# Driver_Channel_DRV8825.net
KiCad netlist of a schematic drawn in Altium Designer
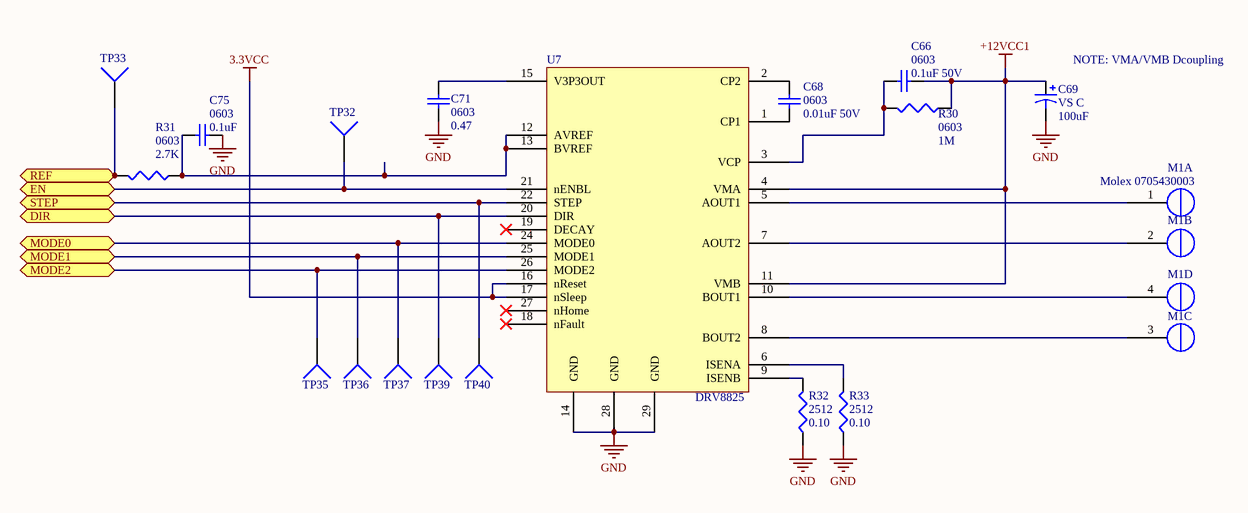
[diagram p0: Driver Channel DRV8825.SchDoc]

(export (version "E")
  (design (tool "Eeschema 10.0.6"))
  (components
    (comp (ref "C66")
      (value "0603")
      (footprint "1608[0603]")
      (description "Capacitor (Semiconductor SIM Model)")
      (fields (field (name "ALTIUM_VALUE") "0.1uF 50V") (field (name "PUBLISHER") "Altium Limited"))
      (libsource (lib "Miscellaneous Devices") (part "Cap Semi"))
    )
    (comp (ref "C68")
      (value "0603")
      (footprint "1608[0603]")
      (description "Capacitor (Semiconductor SIM Model)")
      (fields (field (name "ALTIUM_VALUE") "0.01uF 50V") (field (name "PUBLISHER") "Altium Limited"))
      (libsource (lib "Miscellaneous Devices") (part "Cap Semi"))
    )
    (comp (ref "C69")
      (value "VS C")
      (footprint "Panasonic VS C")
      (description "Polarized Capacitor (Radial)")
      (fields (field (name "ALTIUM_VALUE") "100uF") (field (name "PUBLISHER") "Altium Limited"))
      (libsource (lib "Miscellaneous Devices") (part "Cap Pol1"))
    )
    (comp (ref "C71")
      (value "0603")
      (footprint "1608[0603]")
      (description "Capacitor (Semiconductor SIM Model)")
      (fields (field (name "ALTIUM_VALUE") "0.47") (field (name "PUBLISHER") "Altium Limited"))
      (libsource (lib "Miscellaneous Devices") (part "Cap Semi"))
    )
    (comp (ref "C75")
      (value "0603")
      (footprint "1608[0603]")
      (description "Capacitor (Semiconductor SIM Model)")
      (fields (field (name "ALTIUM_VALUE") "0.1uF") (field (name "PUBLISHER") "Altium Limited"))
      (libsource (lib "Miscellaneous Devices") (part "Cap Semi"))
    )
    (comp (ref "M1")
      (value "Molex 0705430003")
      (footprint "4POL254")
      (description "Molex 4 Pin Clip Connector")
      (libsource (lib "ZMBo Schematic Library") (part "Molex 0705430003 Alt"))
    )
    (comp (ref "R30")
      (value "0603")
      (footprint "J1-0603")
      (description "Resistor")
      (fields (field (name "ALTIUM_VALUE") "1M") (field (name "PUBLISHER") "Altium Limited"))
      (libsource (lib "Miscellaneous Devices") (part "Res3"))
    )
    (comp (ref "R31")
      (value "0603")
      (footprint "J1-0603")
      (description "Resistor")
      (fields (field (name "ALTIUM_VALUE") "2.7K") (field (name "PUBLISHER") "Altium Limited"))
      (libsource (lib "Miscellaneous Devices") (part "Res3"))
    )
    (comp (ref "R32")
      (value "2512")
      (footprint "Resistor2512")
      (description "Resistor")
      (fields (field (name "ALTIUM_VALUE") "0.10") (field (name "PUBLISHER") "Altium Limited"))
      (libsource (lib "Miscellaneous Devices") (part "Res3"))
    )
    (comp (ref "R33")
      (value "2512")
      (footprint "Resistor2512")
      (description "Resistor")
      (fields (field (name "ALTIUM_VALUE") "0.10") (field (name "PUBLISHER") "Altium Limited"))
      (libsource (lib "Miscellaneous Devices") (part "Res3"))
    )
    (comp (ref "TP32")
      (value "TP4")
      (footprint "TP-2")
      (description "Socket")
      (fields (field (name "PUBLISHER") "Altium Limited"))
      (libsource (lib "ZMBo Schematic Library") (part "Socket"))
    )
    (comp (ref "TP33")
      (value "TP4")
      (footprint "TP-2")
      (description "Socket")
      (fields (field (name "PUBLISHER") "Altium Limited"))
      (libsource (lib "ZMBo Schematic Library") (part "Socket"))
    )
    (comp (ref "TP35")
      (value "TP4")
      (footprint "TP-2")
      (description "Socket")
      (fields (field (name "PUBLISHER") "Altium Limited"))
      (libsource (lib "ZMBo Schematic Library") (part "Socket"))
    )
    (comp (ref "TP36")
      (value "TP4")
      (footprint "TP-2")
      (description "Socket")
      (fields (field (name "PUBLISHER") "Altium Limited"))
      (libsource (lib "ZMBo Schematic Library") (part "Socket"))
    )
    (comp (ref "TP37")
      (value "TP4")
      (footprint "TP-2")
      (description "Socket")
      (fields (field (name "PUBLISHER") "Altium Limited"))
      (libsource (lib "ZMBo Schematic Library") (part "Socket"))
    )
    (comp (ref "TP39")
      (value "TP4")
      (footprint "TP-2")
      (description "Socket")
      (fields (field (name "PUBLISHER") "Altium Limited"))
      (libsource (lib "ZMBo Schematic Library") (part "Socket"))
    )
    (comp (ref "TP40")
      (value "TP4")
      (footprint "TP-2")
      (description "Socket")
      (fields (field (name "PUBLISHER") "Altium Limited"))
      (libsource (lib "ZMBo Schematic Library") (part "Socket"))
    )
    (comp (ref "U7")
      (value "DRV8825")
      (footprint "DRV8825")
      (description "DRV8825 Ti Stepper Driver")
      (libsource (lib "ZMBo Schematic Library") (part "DRV8825"))
    )
  )
  (nets
    (net (code "1") (name "+12VCC1") (class "Default")
      (node (ref "C66") (pin "1") (pinfunction "1_1") (pintype "passive"))
      (node (ref "C69") (pin "1") (pinfunction "1_1") (pintype "passive"))
      (node (ref "R30") (pin "1") (pinfunction "1_1") (pintype "passive"))
      (node (ref "U7") (pin "11") (pinfunction "VMB_11") (pintype "passive"))
      (node (ref "U7") (pin "4") (pinfunction "VMA_4") (pintype "passive"))
    )
    (net (code "2") (name "/DIR") (class "Default")
      (node (ref "TP39") (pin "1") (pinfunction "1_1") (pintype "passive"))
      (node (ref "U7") (pin "20") (pinfunction "DIR_20") (pintype "passive"))
    )
    (net (code "3") (name "/EN") (class "Default")
      (node (ref "TP32") (pin "1") (pinfunction "1_1") (pintype "passive"))
      (node (ref "U7") (pin "21") (pinfunction "nENBL_21") (pintype "passive"))
    )
    (net (code "4") (name "/MODE0") (class "Default")
      (node (ref "TP37") (pin "1") (pinfunction "1_1") (pintype "passive"))
      (node (ref "U7") (pin "24") (pinfunction "MODE0_24") (pintype "passive"))
    )
    (net (code "5") (name "/MODE1") (class "Default")
      (node (ref "TP36") (pin "1") (pinfunction "1_1") (pintype "passive"))
      (node (ref "U7") (pin "25") (pinfunction "MODE1_25") (pintype "passive"))
    )
    (net (code "6") (name "/MODE2") (class "Default")
      (node (ref "TP35") (pin "1") (pinfunction "1_1") (pintype "passive"))
      (node (ref "U7") (pin "26") (pinfunction "MODE2_26") (pintype "passive"))
    )
    (net (code "7") (name "/REF") (class "Default")
      (node (ref "R31") (pin "2") (pinfunction "2_2") (pintype "passive"))
      (node (ref "TP33") (pin "1") (pinfunction "1_1") (pintype "passive"))
    )
    (net (code "8") (name "/STEP") (class "Default")
      (node (ref "TP40") (pin "1") (pinfunction "1_1") (pintype "passive"))
      (node (ref "U7") (pin "22") (pinfunction "STEP_22") (pintype "passive"))
    )
    (net (code "9") (name "3.3VCC") (class "Default")
      (node (ref "U7") (pin "16") (pinfunction "nReset_16") (pintype "passive"))
      (node (ref "U7") (pin "17") (pinfunction "nSleep_17") (pintype "passive"))
    )
    (net (code "10") (name "GND") (class "Default")
      (node (ref "C69") (pin "2") (pinfunction "2_2") (pintype "passive"))
      (node (ref "C71") (pin "1") (pinfunction "1_1") (pintype "passive"))
      (node (ref "C75") (pin "1") (pinfunction "1_1") (pintype "passive"))
      (node (ref "R32") (pin "1") (pinfunction "1_1") (pintype "passive"))
      (node (ref "R33") (pin "1") (pinfunction "1_1") (pintype "passive"))
      (node (ref "U7") (pin "14") (pinfunction "GND_14") (pintype "passive"))
      (node (ref "U7") (pin "28") (pinfunction "GND_28") (pintype "passive"))
      (node (ref "U7") (pin "29") (pinfunction "GND_29") (pintype "passive"))
    )
    (net (code "11") (name "Net-(M1A-OUT2B)") (class "Default")
      (node (ref "M1") (pin "1") (pinfunction "OUT2B_1") (pintype "passive"))
      (node (ref "U7") (pin "5") (pinfunction "AOUT1_5") (pintype "passive"))
    )
    (net (code "12") (name "Net-(M1B-OUT2A)") (class "Default")
      (node (ref "M1") (pin "2") (pinfunction "OUT2A_2") (pintype "passive"))
      (node (ref "U7") (pin "7") (pinfunction "AOUT2_7") (pintype "passive"))
    )
    (net (code "13") (name "Net-(M1C-OUT1A)") (class "Default")
      (node (ref "M1") (pin "3") (pinfunction "OUT1A_3") (pintype "passive"))
      (node (ref "U7") (pin "8") (pinfunction "BOUT2_8") (pintype "passive"))
    )
    (net (code "14") (name "Net-(M1D-OUT1B)") (class "Default")
      (node (ref "M1") (pin "4") (pinfunction "OUT1B_4") (pintype "passive"))
      (node (ref "U7") (pin "10") (pinfunction "BOUT1_10") (pintype "passive"))
    )
    (net (code "15") (name "Net-(U7-AVREF)") (class "Default")
      (node (ref "C75") (pin "2") (pinfunction "2_2") (pintype "passive"))
      (node (ref "R31") (pin "1") (pinfunction "1_1") (pintype "passive"))
      (node (ref "U7") (pin "12") (pinfunction "AVREF_12") (pintype "passive"))
      (node (ref "U7") (pin "13") (pinfunction "BVREF_13") (pintype "passive"))
    )
    (net (code "16") (name "Net-(U7-CP1)") (class "Default")
      (node (ref "C68") (pin "1") (pinfunction "1_1") (pintype "passive"))
      (node (ref "U7") (pin "1") (pinfunction "CP1_1") (pintype "passive"))
    )
    (net (code "17") (name "Net-(U7-CP2)") (class "Default")
      (node (ref "C68") (pin "2") (pinfunction "2_2") (pintype "passive"))
      (node (ref "U7") (pin "2") (pinfunction "CP2_2") (pintype "passive"))
    )
    (net (code "18") (name "Net-(U7-ISENA)") (class "Default")
      (node (ref "R33") (pin "2") (pinfunction "2_2") (pintype "passive"))
      (node (ref "U7") (pin "6") (pinfunction "ISENA_6") (pintype "passive"))
    )
    (net (code "19") (name "Net-(U7-ISENB)") (class "Default")
      (node (ref "R32") (pin "2") (pinfunction "2_2") (pintype "passive"))
      (node (ref "U7") (pin "9") (pinfunction "ISENB_9") (pintype "passive"))
    )
    (net (code "20") (name "Net-(U7-V3P3OUT)") (class "Default")
      (node (ref "C71") (pin "2") (pinfunction "2_2") (pintype "passive"))
      (node (ref "U7") (pin "15") (pinfunction "V3P3OUT_15") (pintype "passive"))
    )
    (net (code "21") (name "Net-(U7-VCP)") (class "Default")
      (node (ref "C66") (pin "2") (pinfunction "2_2") (pintype "passive"))
      (node (ref "R30") (pin "2") (pinfunction "2_2") (pintype "passive"))
      (node (ref "U7") (pin "3") (pinfunction "VCP_3") (pintype "passive"))
    )
    (net (code "22") (name "unconnected-(U7-DECAY-Pad19)") (class "Default")
      (node (ref "U7") (pin "19") (pinfunction "DECAY_19") (pintype "passive+no_connect"))
    )
    (net (code "23") (name "unconnected-(U7-NC-Pad23)") (class "Default")
      (node (ref "U7") (pin "23") (pinfunction "NC_23") (pintype "passive"))
    )
    (net (code "24") (name "unconnected-(U7-nFault-Pad18)") (class "Default")
      (node (ref "U7") (pin "18") (pinfunction "nFault_18") (pintype "passive+no_connect"))
    )
    (net (code "25") (name "unconnected-(U7-nHome-Pad27)") (class "Default")
      (node (ref "U7") (pin "27") (pinfunction "nHome_27") (pintype "passive+no_connect"))
    )
  )
)
